# LiPo_Charger.net
KiCad netlist of a schematic drawn in EAGLE
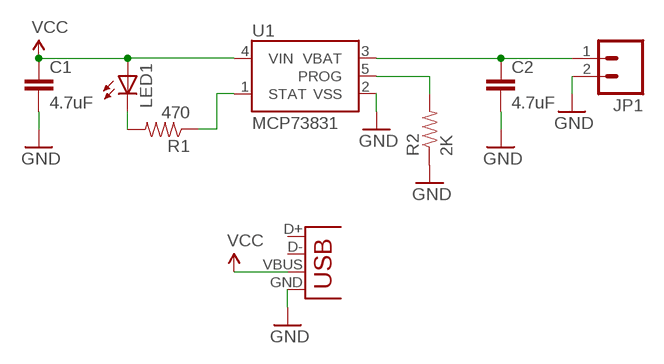
[diagram p0: schematic, sheet 1]

(export (version "E")
  (design (tool "Eeschema 10.0.6"))
  (components
    (comp (ref "C1")
      (value "4.7uF")
      (footprint "eagle-import:1206")
      (libsource (lib "eagle-import") (part "CAP1206"))
    )
    (comp (ref "C2")
      (value "4.7uF")
      (footprint "eagle-import:1206")
      (libsource (lib "eagle-import") (part "CAP1206"))
    )
    (comp (ref "JP1")
      (value "M02POLAR")
      (footprint "eagle-import:MOLEX-1X2")
      (libsource (lib "eagle-import") (part "M02POLAR"))
    )
    (comp (ref "LED1")
      (value "LEDCHIP-LED0603")
      (footprint "eagle-import:CHIP-LED0603")
      (libsource (lib "eagle-import") (part "LEDCHIP-LED0603"))
    )
    (comp (ref "R1")
      (value "470")
      (footprint "eagle-import:0805")
      (libsource (lib "eagle-import") (part "RESISTOR0805-RES"))
    )
    (comp (ref "R2")
      (value "2K")
      (footprint "eagle-import:0805")
      (libsource (lib "eagle-import") (part "RESISTOR0805-RES"))
    )
    (comp (ref "U1")
      (value "MCP73831")
      (footprint "eagle-import:SOT23-5")
      (libsource (lib "eagle-import") (part "MCP73831"))
    )
    (comp (ref "X1")
      (value "USB")
      (footprint "eagle-import:USB-A-MALE-SMT")
      (libsource (lib "eagle-import") (part "USB"))
    )
  )
  (nets
    (net (code "1") (name "GND") (class "Default")
      (node (ref "C1") (pin "2") (pinfunction "2_2") (pintype "passive"))
      (node (ref "C2") (pin "2") (pinfunction "2_2") (pintype "passive"))
      (node (ref "JP1") (pin "2") (pinfunction "2_2") (pintype "passive"))
      (node (ref "R2") (pin "1") (pinfunction "1_1") (pintype "passive"))
      (node (ref "U1") (pin "2") (pinfunction "VSS_2") (pintype "power_in"))
      (node (ref "X1") (pin "GND") (pinfunction "GND_GND") (pintype "bidirectional"))
    )
    (net (code "2") (name "Net-(LED1-PadC)") (class "Default")
      (node (ref "LED1") (pin "C") (pinfunction "C_C") (pintype "passive"))
      (node (ref "R1") (pin "2") (pinfunction "2_2") (pintype "passive"))
    )
    (net (code "3") (name "Net-(U1-PROG)") (class "Default")
      (node (ref "R2") (pin "2") (pinfunction "2_2") (pintype "passive"))
      (node (ref "U1") (pin "5") (pinfunction "PROG_5") (pintype "input"))
    )
    (net (code "4") (name "Net-(U1-STAT)") (class "Default")
      (node (ref "R1") (pin "1") (pinfunction "1_1") (pintype "passive"))
      (node (ref "U1") (pin "1") (pinfunction "STAT_1") (pintype "output"))
    )
    (net (code "5") (name "Net-(U1-VBAT)") (class "Default")
      (node (ref "C2") (pin "1") (pinfunction "1_1") (pintype "passive"))
      (node (ref "JP1") (pin "1") (pinfunction "1_1") (pintype "passive"))
      (node (ref "U1") (pin "3") (pinfunction "VBAT_3") (pintype "power_in"))
    )
    (net (code "6") (name "VCC") (class "Default")
      (node (ref "C1") (pin "1") (pinfunction "1_1") (pintype "passive"))
      (node (ref "LED1") (pin "A") (pinfunction "A_A") (pintype "passive"))
      (node (ref "U1") (pin "4") (pinfunction "VIN_4") (pintype "power_in"))
      (node (ref "X1") (pin "VBUS") (pinfunction "VBUS_VBUS") (pintype "bidirectional"))
    )
    (net (code "7") (name "unconnected-(X1-PadD+)") (class "Default")
      (node (ref "X1") (pin "D+") (pinfunction "D+_D+") (pintype "bidirectional"))
    )
    (net (code "8") (name "unconnected-(X1-PadD-)") (class "Default")
      (node (ref "X1") (pin "D-") (pinfunction "D-_D-") (pintype "bidirectional"))
    )
  )
)
